# 20190320.net
KiCad netlist of a schematic drawn in EAGLE
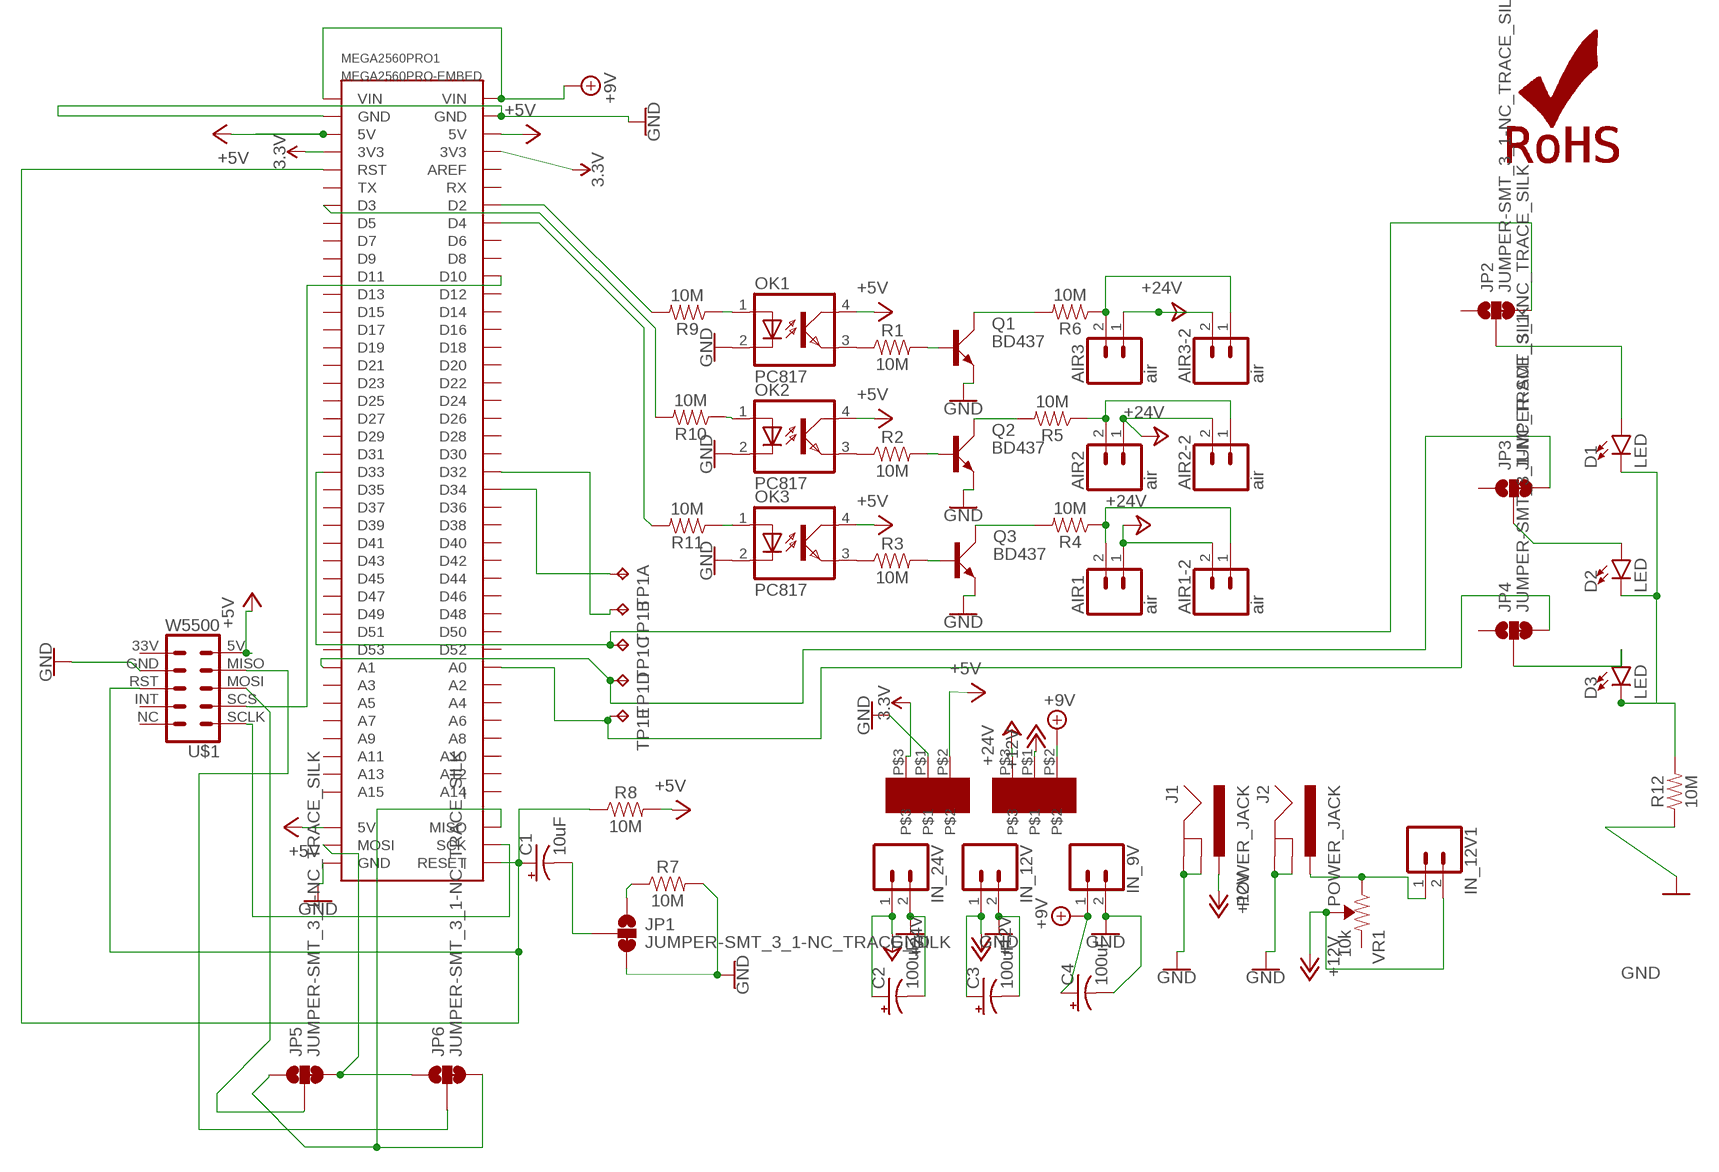
[diagram p0: schematic, sheet 1]

(export (version "E")
  (design (tool "Eeschema 10.0.6"))
  (components
    (comp (ref "AIR1")
      (value "air")
      (footprint "eagle-import:MOLEX-1X2_LOCK")
      (libsource (lib "eagle-import") (part "CONN_02POLAR_LOCK"))
    )
    (comp (ref "AIR1-2")
      (value "air")
      (footprint "eagle-import:1X02")
      (libsource (lib "eagle-import") (part "CONN_02"))
    )
    (comp (ref "AIR2")
      (value "air")
      (footprint "eagle-import:MOLEX-1X2_LOCK")
      (libsource (lib "eagle-import") (part "CONN_02POLAR_LOCK"))
    )
    (comp (ref "AIR2-2")
      (value "air")
      (footprint "eagle-import:1X02")
      (libsource (lib "eagle-import") (part "CONN_02"))
    )
    (comp (ref "AIR3")
      (value "air")
      (footprint "eagle-import:MOLEX-1X2_LOCK")
      (libsource (lib "eagle-import") (part "CONN_02POLAR_LOCK"))
    )
    (comp (ref "AIR3-2")
      (value "air")
      (footprint "eagle-import:1X02")
      (libsource (lib "eagle-import") (part "CONN_02"))
    )
    (comp (ref "C1")
      (value "10uF")
      (footprint "eagle-import:CPOL-RADIAL-2.5MM-5MM-KIT")
      (libsource (lib "eagle-import") (part "10UF-POLAR-RADIAL-2.5MM-KIT-25V-20%"))
    )
    (comp (ref "C2")
      (value "100uF")
      (footprint "eagle-import:CPOL-RADIAL-2.5MM-6.5MM")
      (libsource (lib "eagle-import") (part "100UF-POLAR-RADIAL-2.5MM-25V-20%"))
    )
    (comp (ref "C3")
      (value "100uF")
      (footprint "eagle-import:CPOL-RADIAL-2.5MM-6.5MM")
      (libsource (lib "eagle-import") (part "100UF-POLAR-RADIAL-2.5MM-25V-20%"))
    )
    (comp (ref "C4")
      (value "100uF")
      (footprint "eagle-import:CPOL-RADIAL-2.5MM-6.5MM")
      (libsource (lib "eagle-import") (part "100UF-POLAR-RADIAL-2.5MM-25V-20%"))
    )
    (comp (ref "D1")
      (value "LED")
      (footprint "eagle-import:LED_5MM")
      (libsource (lib "eagle-import") (part "LED5MM"))
    )
    (comp (ref "D2")
      (value "LED")
      (footprint "eagle-import:LED_5MM")
      (libsource (lib "eagle-import") (part "LED5MM"))
    )
    (comp (ref "D3")
      (value "LED")
      (footprint "eagle-import:LED_5MM")
      (libsource (lib "eagle-import") (part "LED5MM"))
    )
    (comp (ref "IN_9V")
      (value "CONN_02POLAR_LOCK")
      (footprint "eagle-import:MOLEX-1X2_LOCK")
      (libsource (lib "eagle-import") (part "CONN_02POLAR_LOCK"))
    )
    (comp (ref "IN_12V")
      (value "CONN_02POLAR_LOCK")
      (footprint "eagle-import:MOLEX-1X2_LOCK")
      (libsource (lib "eagle-import") (part "CONN_02POLAR_LOCK"))
    )
    (comp (ref "IN_12V1")
      (value "CONN_02POLAR_LOCK")
      (footprint "eagle-import:MOLEX-1X2_LOCK")
      (libsource (lib "eagle-import") (part "CONN_02POLAR_LOCK"))
    )
    (comp (ref "IN_24V")
      (value "CONN_02POLAR_LOCK")
      (footprint "eagle-import:MOLEX-1X2_LOCK")
      (libsource (lib "eagle-import") (part "CONN_02POLAR_LOCK"))
    )
    (comp (ref "J1")
      (value "POWER_JACK")
      (footprint "eagle-import:POWER_JACK_PTH")
      (libsource (lib "eagle-import") (part "POWER_JACK"))
    )
    (comp (ref "J2")
      (value "POWER_JACK")
      (footprint "eagle-import:POWER_JACK_PTH")
      (libsource (lib "eagle-import") (part "POWER_JACK"))
    )
    (comp (ref "JP1")
      (value "JUMPER-SMT_3_1-NC_TRACE_SILK")
      (footprint "eagle-import:SMT-JUMPER_3_1-NC_TRACE_SILK")
      (libsource (lib "eagle-import") (part "JUMPER-SMT_3_1-NC_TRACE_SILK"))
    )
    (comp (ref "JP2")
      (value "JUMPER-SMT_3_1-NC_TRACE_SILK")
      (footprint "eagle-import:SMT-JUMPER_3_1-NC_TRACE_SILK")
      (libsource (lib "eagle-import") (part "JUMPER-SMT_3_1-NC_TRACE_SILK"))
    )
    (comp (ref "JP3")
      (value "JUMPER-SMT_3_1-NC_TRACE_SILK")
      (footprint "eagle-import:SMT-JUMPER_3_1-NC_TRACE_SILK")
      (libsource (lib "eagle-import") (part "JUMPER-SMT_3_1-NC_TRACE_SILK"))
    )
    (comp (ref "JP4")
      (value "JUMPER-SMT_3_1-NC_TRACE_SILK")
      (footprint "eagle-import:SMT-JUMPER_3_1-NC_TRACE_SILK")
      (libsource (lib "eagle-import") (part "JUMPER-SMT_3_1-NC_TRACE_SILK"))
    )
    (comp (ref "JP5")
      (value "JUMPER-SMT_3_1-NC_TRACE_SILK")
      (footprint "eagle-import:SMT-JUMPER_3_1-NC_TRACE_SILK")
      (libsource (lib "eagle-import") (part "JUMPER-SMT_3_1-NC_TRACE_SILK"))
    )
    (comp (ref "JP6")
      (value "JUMPER-SMT_3_1-NC_TRACE_SILK")
      (footprint "eagle-import:SMT-JUMPER_3_1-NC_TRACE_SILK")
      (libsource (lib "eagle-import") (part "JUMPER-SMT_3_1-NC_TRACE_SILK"))
    )
    (comp (ref "LOGO1")
      (value "ROHS_LOGO")
      (footprint "eagle-import:ROHS_LOGO_0.18_IN")
      (libsource (lib "eagle-import") (part "ROHS_LOGO"))
    )
    (comp (ref "MEGA2560PRO1")
      (value "MEGA2560PRO-EMBED")
      (footprint "eagle-import:MEGA2560PRO-EMBED")
      (libsource (lib "eagle-import") (part "MEGA2560PRO-EMBED"))
    )
    (comp (ref "OK1")
      (value "PC817")
      (footprint "eagle-import:DIL04")
      (fields (field (name "MPN") "PC817X4J000F"))
      (libsource (lib "eagle-import") (part "PC817"))
    )
    (comp (ref "OK2")
      (value "PC817")
      (footprint "eagle-import:DIL04")
      (fields (field (name "MPN") "PC817X4J000F"))
      (libsource (lib "eagle-import") (part "PC817"))
    )
    (comp (ref "OK3")
      (value "PC817")
      (footprint "eagle-import:DIL04")
      (fields (field (name "MPN") "PC817X4J000F"))
      (libsource (lib "eagle-import") (part "PC817"))
    )
    (comp (ref "Q1")
      (value "BD437")
      (footprint "eagle-import:TO126AV")
      (libsource (lib "eagle-import") (part "BD437"))
    )
    (comp (ref "Q2")
      (value "BD437")
      (footprint "eagle-import:TO126AV")
      (libsource (lib "eagle-import") (part "BD437"))
    )
    (comp (ref "Q3")
      (value "BD437")
      (footprint "eagle-import:TO126AV")
      (libsource (lib "eagle-import") (part "BD437"))
    )
    (comp (ref "R1")
      (value "10M")
      (footprint "eagle-import:AXIAL-0.3")
      (libsource (lib "eagle-import") (part "10MOHM-HORIZ-1/4W-5%"))
    )
    (comp (ref "R2")
      (value "10M")
      (footprint "eagle-import:AXIAL-0.3")
      (libsource (lib "eagle-import") (part "10MOHM-HORIZ-1/4W-5%"))
    )
    (comp (ref "R3")
      (value "10M")
      (footprint "eagle-import:AXIAL-0.3")
      (libsource (lib "eagle-import") (part "10MOHM-HORIZ-1/4W-5%"))
    )
    (comp (ref "R4")
      (value "10M")
      (footprint "eagle-import:AXIAL-0.3")
      (libsource (lib "eagle-import") (part "10MOHM-HORIZ-1/4W-5%"))
    )
    (comp (ref "R5")
      (value "10M")
      (footprint "eagle-import:AXIAL-0.3")
      (libsource (lib "eagle-import") (part "10MOHM-HORIZ-1/4W-5%"))
    )
    (comp (ref "R6")
      (value "10M")
      (footprint "eagle-import:AXIAL-0.3")
      (libsource (lib "eagle-import") (part "10MOHM-HORIZ-1/4W-5%"))
    )
    (comp (ref "R7")
      (value "10M")
      (footprint "eagle-import:AXIAL-0.3")
      (libsource (lib "eagle-import") (part "10MOHM-HORIZ-1/4W-5%"))
    )
    (comp (ref "R8")
      (value "10M")
      (footprint "eagle-import:AXIAL-0.3")
      (libsource (lib "eagle-import") (part "10MOHM-HORIZ-1/4W-5%"))
    )
    (comp (ref "R9")
      (value "10M")
      (footprint "eagle-import:AXIAL-0.3")
      (libsource (lib "eagle-import") (part "10MOHM-HORIZ-1/4W-5%"))
    )
    (comp (ref "R10")
      (value "10M")
      (footprint "eagle-import:AXIAL-0.3")
      (libsource (lib "eagle-import") (part "10MOHM-HORIZ-1/4W-5%"))
    )
    (comp (ref "R11")
      (value "10M")
      (footprint "eagle-import:AXIAL-0.3")
      (libsource (lib "eagle-import") (part "10MOHM-HORIZ-1/4W-5%"))
    )
    (comp (ref "R12")
      (value "10M")
      (footprint "eagle-import:AXIAL-0.3")
      (libsource (lib "eagle-import") (part "10MOHM-HORIZ-1/4W-5%"))
    )
    (comp (ref "TP1")
      (value "TP5P5-25-13")
      (footprint "eagle-import:P5-25-13")
      (libsource (lib "eagle-import") (part "TP5P5-25-13"))
    )
    (comp (ref "U$1")
      (value "W5500")
      (footprint "eagle-import:W5500")
      (libsource (lib "eagle-import") (part "W5500"))
    )
    (comp (ref "U$2")
      (value "AC_3PINAC3PIN7MM")
      (footprint "eagle-import:AC3PIN7MM")
      (libsource (lib "eagle-import") (part "AC_3PINAC3PIN7MM"))
    )
    (comp (ref "U$4")
      (value "AC_3PINAC3PIN7MM")
      (footprint "eagle-import:AC3PIN7MM")
      (libsource (lib "eagle-import") (part "AC_3PINAC3PIN7MM"))
    )
    (comp (ref "VR1")
      (value "10k")
      (footprint "eagle-import:TRIMPOT-PTH-3386U")
      (libsource (lib "eagle-import") (part "TRIMPOT-PTH-10MM-KNOB-1/2W-10%"))
    )
  )
  (nets
    (net (code "1") (name "+5V") (class "Default")
      (node (ref "MEGA2560PRO1") (pin "5V@1") (pinfunction "5V_5V@1") (pintype "bidirectional"))
      (node (ref "MEGA2560PRO1") (pin "5V@2") (pinfunction "5V_5V@2") (pintype "bidirectional"))
      (node (ref "MEGA2560PRO1") (pin "5V@3") (pinfunction "5V_5V@3") (pintype "bidirectional"))
      (node (ref "OK1") (pin "4") (pinfunction "COL_4") (pintype "passive"))
      (node (ref "OK2") (pin "4") (pinfunction "COL_4") (pintype "passive"))
      (node (ref "OK3") (pin "4") (pinfunction "COL_4") (pintype "passive"))
      (node (ref "R8") (pin "P$2") (pinfunction "2_P$2") (pintype "passive"))
      (node (ref "U$1") (pin "5V") (pinfunction "9_5V") (pintype "passive"))
      (node (ref "U$4") (pin "P$2") (pinfunction "P$2_P$2") (pintype "bidirectional"))
    )
    (net (code "2") (name "+9V") (class "Default")
      (node (ref "C4") (pin "1") (pinfunction "+_1") (pintype "passive"))
      (node (ref "IN_9V") (pin "1") (pinfunction "1_1") (pintype "passive"))
      (node (ref "MEGA2560PRO1") (pin "VIN@1") (pinfunction "VIN_VIN@1") (pintype "bidirectional"))
      (node (ref "MEGA2560PRO1") (pin "VIN@2") (pinfunction "VIN_VIN@2") (pintype "bidirectional"))
      (node (ref "U$2") (pin "P$2") (pinfunction "P$2_P$2") (pintype "bidirectional"))
    )
    (net (code "3") (name "+12V") (class "Default")
      (node (ref "C3") (pin "1") (pinfunction "+_1") (pintype "passive"))
      (node (ref "IN_12V") (pin "1") (pinfunction "1_1") (pintype "passive"))
      (node (ref "IN_12V1") (pin "2") (pinfunction "2_2") (pintype "passive"))
      (node (ref "J1") (pin "PWR") (pinfunction "PWR_PWR") (pintype "bidirectional"))
      (node (ref "U$2") (pin "P$1") (pinfunction "P$1_P$1") (pintype "bidirectional"))
      (node (ref "VR1") (pin "2") (pinfunction "WIPER_2") (pintype "passive"))
    )
    (net (code "4") (name "+24V") (class "Default")
      (node (ref "AIR1") (pin "1") (pinfunction "1_1") (pintype "passive"))
      (node (ref "AIR1-2") (pin "2") (pinfunction "2_2") (pintype "passive"))
      (node (ref "AIR2") (pin "1") (pinfunction "1_1") (pintype "passive"))
      (node (ref "AIR2-2") (pin "2") (pinfunction "2_2") (pintype "passive"))
      (node (ref "AIR3") (pin "1") (pinfunction "1_1") (pintype "passive"))
      (node (ref "AIR3-2") (pin "2") (pinfunction "2_2") (pintype "passive"))
      (node (ref "C2") (pin "1") (pinfunction "+_1") (pintype "passive"))
      (node (ref "IN_24V") (pin "1") (pinfunction "1_1") (pintype "passive"))
      (node (ref "U$2") (pin "P$3") (pinfunction "P$3_P$3") (pintype "bidirectional"))
    )
    (net (code "5") (name "3.3V") (class "Default")
      (node (ref "MEGA2560PRO1") (pin "3V3@1") (pinfunction "3V3_3V3@1") (pintype "bidirectional"))
      (node (ref "MEGA2560PRO1") (pin "3V3@2") (pinfunction "3V3_3V3@2") (pintype "bidirectional"))
      (node (ref "U$4") (pin "P$3") (pinfunction "P$3_P$3") (pintype "bidirectional"))
    )
    (net (code "6") (name "GND") (class "Default")
      (node (ref "C2") (pin "2") (pinfunction "-_2") (pintype "passive"))
      (node (ref "C3") (pin "2") (pinfunction "-_2") (pintype "passive"))
      (node (ref "C4") (pin "2") (pinfunction "-_2") (pintype "passive"))
      (node (ref "IN_12V") (pin "2") (pinfunction "2_2") (pintype "passive"))
      (node (ref "IN_24V") (pin "2") (pinfunction "2_2") (pintype "passive"))
      (node (ref "IN_9V") (pin "2") (pinfunction "2_2") (pintype "passive"))
      (node (ref "J1") (pin "GND") (pinfunction "GND_GND") (pintype "bidirectional"))
      (node (ref "J1") (pin "GNDBREAK") (pinfunction "GNDBREAK_GNDBREAK") (pintype "bidirectional"))
      (node (ref "J2") (pin "GND") (pinfunction "GND_GND") (pintype "bidirectional"))
      (node (ref "J2") (pin "GNDBREAK") (pinfunction "GNDBREAK_GNDBREAK") (pintype "bidirectional"))
      (node (ref "JP1") (pin "3") (pinfunction "3_3") (pintype "passive"))
      (node (ref "MEGA2560PRO1") (pin "GND@1") (pinfunction "GND_GND@1") (pintype "bidirectional"))
      (node (ref "MEGA2560PRO1") (pin "GND@2") (pinfunction "GND_GND@2") (pintype "bidirectional"))
      (node (ref "MEGA2560PRO1") (pin "GND@3") (pinfunction "GND_GND@3") (pintype "bidirectional"))
      (node (ref "OK1") (pin "2") (pinfunction "C_2") (pintype "passive"))
      (node (ref "OK2") (pin "2") (pinfunction "C_2") (pintype "passive"))
      (node (ref "OK3") (pin "2") (pinfunction "C_2") (pintype "passive"))
      (node (ref "Q1") (pin "E") (pinfunction "E_E") (pintype "passive"))
      (node (ref "Q2") (pin "E") (pinfunction "E_E") (pintype "passive"))
      (node (ref "Q3") (pin "E") (pinfunction "E_E") (pintype "passive"))
      (node (ref "R12") (pin "P$1") (pinfunction "1_P$1") (pintype "passive"))
      (node (ref "R7") (pin "P$2") (pinfunction "2_P$2") (pintype "passive"))
      (node (ref "U$1") (pin "GND") (pinfunction "8_GND") (pintype "passive"))
      (node (ref "U$4") (pin "P$1") (pinfunction "P$1_P$1") (pintype "bidirectional"))
    )
    (net (code "7") (name "Net-(C1-+)") (class "Default")
      (node (ref "C1") (pin "1") (pinfunction "+_1") (pintype "passive"))
      (node (ref "MEGA2560PRO1") (pin "RESET") (pinfunction "RESET_RESET") (pintype "bidirectional"))
      (node (ref "MEGA2560PRO1") (pin "RST") (pinfunction "RST_RST") (pintype "bidirectional"))
      (node (ref "R8") (pin "P$1") (pinfunction "1_P$1") (pintype "passive"))
      (node (ref "U$1") (pin "RST") (pinfunction "6_RST") (pintype "passive"))
    )
    (net (code "8") (name "Net-(C1--)") (class "Default")
      (node (ref "C1") (pin "2") (pinfunction "-_2") (pintype "passive"))
      (node (ref "JP1") (pin "2") (pinfunction "2_2") (pintype "passive"))
    )
    (net (code "9") (name "Net-(D1-C)") (class "Default")
      (node (ref "D1") (pin "K") (pinfunction "C_K") (pintype "passive"))
      (node (ref "D2") (pin "K") (pinfunction "C_K") (pintype "passive"))
      (node (ref "D3") (pin "K") (pinfunction "C_K") (pintype "passive"))
      (node (ref "R12") (pin "P$2") (pinfunction "2_P$2") (pintype "passive"))
    )
    (net (code "10") (name "Net-(D1-PadA)") (class "Default")
      (node (ref "D1") (pin "A") (pinfunction "A_A") (pintype "passive"))
      (node (ref "JP2") (pin "2") (pinfunction "2_2") (pintype "passive"))
    )
    (net (code "11") (name "Net-(D2-PadA)") (class "Default")
      (node (ref "D2") (pin "A") (pinfunction "A_A") (pintype "passive"))
      (node (ref "JP3") (pin "2") (pinfunction "2_2") (pintype "passive"))
    )
    (net (code "12") (name "Net-(D3-PadA)") (class "Default")
      (node (ref "D3") (pin "A") (pinfunction "A_A") (pintype "passive"))
      (node (ref "JP4") (pin "2") (pinfunction "2_2") (pintype "passive"))
    )
    (net (code "13") (name "Net-(JP5-Pad1)") (class "Default")
      (node (ref "JP5") (pin "1") (pinfunction "1_1") (pintype "passive"))
      (node (ref "JP6") (pin "3") (pinfunction "3_3") (pintype "passive"))
      (node (ref "MEGA2560PRO1") (pin "MISO") (pinfunction "MISO_MISO") (pintype "bidirectional"))
    )
    (net (code "14") (name "Net-(JP5-Pad3)") (class "Default")
      (node (ref "JP5") (pin "3") (pinfunction "3_3") (pintype "passive"))
      (node (ref "JP6") (pin "1") (pinfunction "1_1") (pintype "passive"))
      (node (ref "MEGA2560PRO1") (pin "MOSI") (pinfunction "MOSI_MOSI") (pintype "bidirectional"))
    )
    (net (code "15") (name "Net-(OK1-A)") (class "Default")
      (node (ref "OK1") (pin "1") (pinfunction "A_1") (pintype "passive"))
      (node (ref "R9") (pin "P$1") (pinfunction "1_P$1") (pintype "passive"))
    )
    (net (code "16") (name "Net-(OK1-EMIT)") (class "Default")
      (node (ref "OK1") (pin "3") (pinfunction "EMIT_3") (pintype "passive"))
      (node (ref "R1") (pin "P$1") (pinfunction "1_P$1") (pintype "passive"))
    )
    (net (code "17") (name "Net-(OK2-A)") (class "Default")
      (node (ref "OK2") (pin "1") (pinfunction "A_1") (pintype "passive"))
      (node (ref "R10") (pin "P$1") (pinfunction "1_P$1") (pintype "passive"))
    )
    (net (code "18") (name "Net-(OK2-EMIT)") (class "Default")
      (node (ref "OK2") (pin "3") (pinfunction "EMIT_3") (pintype "passive"))
      (node (ref "R2") (pin "P$1") (pinfunction "1_P$1") (pintype "passive"))
    )
    (net (code "19") (name "Net-(OK3-A)") (class "Default")
      (node (ref "OK3") (pin "1") (pinfunction "A_1") (pintype "passive"))
      (node (ref "R11") (pin "P$1") (pinfunction "1_P$1") (pintype "passive"))
    )
    (net (code "20") (name "Net-(OK3-EMIT)") (class "Default")
      (node (ref "OK3") (pin "3") (pinfunction "EMIT_3") (pintype "passive"))
      (node (ref "R3") (pin "P$1") (pinfunction "1_P$1") (pintype "passive"))
    )
    (net (code "21") (name "Net-(R1-2)") (class "Default")
      (node (ref "Q1") (pin "B") (pinfunction "B_B") (pintype "passive"))
      (node (ref "R1") (pin "P$2") (pinfunction "2_P$2") (pintype "passive"))
    )
    (net (code "22") (name "Net-(R2-2)") (class "Default")
      (node (ref "Q2") (pin "B") (pinfunction "B_B") (pintype "passive"))
      (node (ref "R2") (pin "P$2") (pinfunction "2_P$2") (pintype "passive"))
    )
    (net (code "23") (name "Net-(R3-2)") (class "Default")
      (node (ref "Q3") (pin "B") (pinfunction "B_B") (pintype "passive"))
      (node (ref "R3") (pin "P$2") (pinfunction "2_P$2") (pintype "passive"))
    )
    (net (code "24") (name "Net-(R4-1)") (class "Default")
      (node (ref "AIR1") (pin "2") (pinfunction "2_2") (pintype "passive"))
      (node (ref "AIR1-2") (pin "1") (pinfunction "1_1") (pintype "passive"))
      (node (ref "R4") (pin "P$1") (pinfunction "1_P$1") (pintype "passive"))
    )
    (net (code "25") (name "Net-(R4-2)") (class "Default")
      (node (ref "Q3") (pin "C") (pinfunction "C_C") (pintype "passive"))
      (node (ref "R4") (pin "P$2") (pinfunction "2_P$2") (pintype "passive"))
    )
    (net (code "26") (name "Net-(R5-1)") (class "Default")
      (node (ref "AIR2") (pin "2") (pinfunction "2_2") (pintype "passive"))
      (node (ref "AIR2-2") (pin "1") (pinfunction "1_1") (pintype "passive"))
      (node (ref "R5") (pin "P$1") (pinfunction "1_P$1") (pintype "passive"))
    )
    (net (code "27") (name "Net-(R5-2)") (class "Default")
      (node (ref "Q2") (pin "C") (pinfunction "C_C") (pintype "passive"))
      (node (ref "R5") (pin "P$2") (pinfunction "2_P$2") (pintype "passive"))
    )
    (net (code "28") (name "Net-(R6-1)") (class "Default")
      (node (ref "AIR3") (pin "2") (pinfunction "2_2") (pintype "passive"))
      (node (ref "AIR3-2") (pin "1") (pinfunction "1_1") (pintype "passive"))
      (node (ref "R6") (pin "P$1") (pinfunction "1_P$1") (pintype "passive"))
    )
    (net (code "29") (name "Net-(R6-2)") (class "Default")
      (node (ref "Q1") (pin "C") (pinfunction "C_C") (pintype "passive"))
      (node (ref "R6") (pin "P$2") (pinfunction "2_P$2") (pintype "passive"))
    )
    (net (code "30") (name "Net-(R7-1)") (class "Default")
      (node (ref "JP1") (pin "1") (pinfunction "1_1") (pintype "passive"))
      (node (ref "R7") (pin "P$1") (pinfunction "1_P$1") (pintype "passive"))
    )
    (net (code "31") (name "Net-(R9-2)") (class "Default")
      (node (ref "MEGA2560PRO1") (pin "D2") (pinfunction "D2_D2") (pintype "bidirectional"))
      (node (ref "R9") (pin "P$2") (pinfunction "2_P$2") (pintype "passive"))
    )
    (net (code "32") (name "Net-(R10-2)") (class "Default")
      (node (ref "MEGA2560PRO1") (pin "D3") (pinfunction "D3_D3") (pintype "bidirectional"))
      (node (ref "R10") (pin "P$2") (pinfunction "2_P$2") (pintype "passive"))
    )
    (net (code "33") (name "Net-(R11-2)") (class "Default")
      (node (ref "MEGA2560PRO1") (pin "D4") (pinfunction "D4_D4") (pintype "bidirectional"))
      (node (ref "R11") (pin "P$2") (pinfunction "2_P$2") (pintype "passive"))
    )
    (net (code "34") (name "Net-(TP1A-TP)") (class "Default")
      (node (ref "MEGA2560PRO1") (pin "D34") (pinfunction "D34_D34") (pintype "bidirectional"))
      (node (ref "TP1") (pin "TP-1") (pinfunction "TP_TP-1") (pintype "input"))
    )
    (net (code "35") (name "Net-(TP1B-TP)") (class "Default")
      (node (ref "MEGA2560PRO1") (pin "D32") (pinfunction "D32_D32") (pintype "bidirectional"))
      (node (ref "TP1") (pin "TP-2") (pinfunction "TP_TP-2") (pintype "input"))
    )
    (net (code "36") (name "Net-(TP1C-TP)") (class "Default")
      (node (ref "JP2") (pin "3") (pinfunction "3_3") (pintype "passive"))
      (node (ref "MEGA2560PRO1") (pin "D33") (pinfunction "D33_D33") (pintype "bidirectional"))
      (node (ref "TP1") (pin "TP-3") (pinfunction "TP_TP-3") (pintype "input"))
    )
    (net (code "37") (name "Net-(TP1D-TP)") (class "Default")
      (node (ref "JP3") (pin "3") (pinfunction "3_3") (pintype "passive"))
      (node (ref "MEGA2560PRO1") (pin "A1") (pinfunction "A1_A1") (pintype "bidirectional"))
      (node (ref "TP1") (pin "TP-4") (pinfunction "TP_TP-4") (pintype "input"))
    )
    (net (code "38") (name "Net-(TP1E-TP)") (class "Default")
      (node (ref "JP4") (pin "3") (pinfunction "3_3") (pintype "passive"))
      (node (ref "MEGA2560PRO1") (pin "A0") (pinfunction "A0_A0") (pintype "bidirectional"))
      (node (ref "TP1") (pin "TP-5") (pinfunction "TP_TP-5") (pintype "input"))
    )
    (net (code "39") (name "Net-(U$1-3)") (class "Default")
      (node (ref "MEGA2560PRO1") (pin "D10") (pinfunction "D10_D10") (pintype "bidirectional"))
      (node (ref "U$1") (pin "SCS") (pinfunction "3_SCS") (pintype "passive"))
    )
    (net (code "40") (name "Net-(U$1-5)") (class "Default")
      (node (ref "JP5") (pin "2") (pinfunction "2_2") (pintype "passive"))
      (node (ref "U$1") (pin "MOSI") (pinfunction "5_MOSI") (pintype "passive"))
    )
    (net (code "41") (name "Net-(U$1-7)") (class "Default")
      (node (ref "JP6") (pin "2") (pinfunction "2_2") (pintype "passive"))
      (node (ref "U$1") (pin "MISO") (pinfunction "7_MISO") (pintype "passive"))
    )
    (net (code "42") (name "Net-(U$1-33V)") (class "Default")
      (node (ref "MEGA2560PRO1") (pin "SCK") (pinfunction "SCK_SCK") (pintype "bidirectional"))
      (node (ref "U$1") (pin "SCLK") (pinfunction "33V_SCLK") (pintype "passive"))
    )
    (net (code "43") (name "Net-(VR1-CW)") (class "Default")
      (node (ref "IN_12V1") (pin "1") (pinfunction "1_1") (pintype "passive"))
      (node (ref "J2") (pin "PWR") (pinfunction "PWR_PWR") (pintype "bidirectional"))
      (node (ref "VR1") (pin "3") (pinfunction "CW_3") (pintype "passive"))
    )
    (net (code "44") (name "unconnected-(JP2-Pad1)") (class "Default")
      (node (ref "JP2") (pin "1") (pinfunction "1_1") (pintype "passive"))
    )
    (net (code "45") (name "unconnected-(JP3-Pad1)") (class "Default")
      (node (ref "JP3") (pin "1") (pinfunction "1_1") (pintype "passive"))
    )
    (net (code "46") (name "unconnected-(JP4-Pad1)") (class "Default")
      (node (ref "JP4") (pin "1") (pinfunction "1_1") (pintype "passive"))
    )
    (net (code "47") (name "unconnected-(MEGA2560PRO1-PadA2)") (class "Default")
      (node (ref "MEGA2560PRO1") (pin "A2") (pinfunction "A2_A2") (pintype "bidirectional"))
    )
    (net (code "48") (name "unconnected-(MEGA2560PRO1-PadA3)") (class "Default")
      (node (ref "MEGA2560PRO1") (pin "A3") (pinfunction "A3_A3") (pintype "bidirectional"))
    )
    (net (code "49") (name "unconnected-(MEGA2560PRO1-PadA4)") (class "Default")
      (node (ref "MEGA2560PRO1") (pin "A4") (pinfunction "A4_A4") (pintype "bidirectional"))
    )
    (net (code "50") (name "unconnected-(MEGA2560PRO1-PadA5)") (class "Default")
      (node (ref "MEGA2560PRO1") (pin "A5") (pinfunction "A5_A5") (pintype "bidirectional"))
    )
    (net (code "51") (name "unconnected-(MEGA2560PRO1-PadA6)") (class "Default")
      (node (ref "MEGA2560PRO1") (pin "A6") (pinfunction "A6_A6") (pintype "bidirectional"))
    )
    (net (code "52") (name "unconnected-(MEGA2560PRO1-PadA7)") (class "Default")
      (node (ref "MEGA2560PRO1") (pin "A7") (pinfunction "A7_A7") (pintype "bidirectional"))
    )
    (net (code "53") (name "unconnected-(MEGA2560PRO1-PadA8)") (class "Default")
      (node (ref "MEGA2560PRO1") (pin "A8") (pinfunction "A8_A8") (pintype "bidirectional"))
    )
    (net (code "54") (name "unconnected-(MEGA2560PRO1-PadA9)") (class "Default")
      (node (ref "MEGA2560PRO1") (pin "A9") (pinfunction "A9_A9") (pintype "bidirectional"))
    )
    (net (code "55") (name "unconnected-(MEGA2560PRO1-PadA10)") (class "Default")
      (node (ref "MEGA2560PRO1") (pin "A10") (pinfunction "A10_A10") (pintype "bidirectional"))
    )
    (net (code "56") (name "unconnected-(MEGA2560PRO1-PadA11)") (class "Default")
      (node (ref "MEGA2560PRO1") (pin "A11") (pinfunction "A11_A11") (pintype "bidirectional"))
    )
    (net (code "57") (name "unconnected-(MEGA2560PRO1-PadA12)") (class "Default")
      (node (ref "MEGA2560PRO1") (pin "A12") (pinfunction "A12_A12") (pintype "bidirectional"))
    )
    (net (code "58") (name "unconnected-(MEGA2560PRO1-PadA13)") (class "Default")
      (node (ref "MEGA2560PRO1") (pin "A13") (pinfunction "A13_A13") (pintype "bidirectional"))
    )
    (net (code "59") (name "unconnected-(MEGA2560PRO1-PadA14)") (class "Default")
      (node (ref "MEGA2560PRO1") (pin "A14") (pinfunction "A14_A14") (pintype "bidirectional"))
    )
    (net (code "60") (name "unconnected-(MEGA2560PRO1-PadA15)") (class "Default")
      (node (ref "MEGA2560PRO1") (pin "A15") (pinfunction "A15_A15") (pintype "bidirectional"))
    )
    (net (code "61") (name "unconnected-(MEGA2560PRO1-PadAREF)") (class "Default")
      (node (ref "MEGA2560PRO1") (pin "AREF") (pinfunction "AREF_AREF") (pintype "bidirectional"))
    )
    (net (code "62") (name "unconnected-(MEGA2560PRO1-PadD5)") (class "Default")
      (node (ref "MEGA2560PRO1") (pin "D5") (pinfunction "D5_D5") (pintype "bidirectional"))
    )
    (net (code "63") (name "unconnected-(MEGA2560PRO1-PadD6)") (class "Default")
      (node (ref "MEGA2560PRO1") (pin "D6") (pinfunction "D6_D6") (pintype "bidirectional"))
    )
    (net (code "64") (name "unconnected-(MEGA2560PRO1-PadD7)") (class "Default")
      (node (ref "MEGA2560PRO1") (pin "D7") (pinfunction "D7_D7") (pintype "bidirectional"))
    )
    (net (code "65") (name "unconnected-(MEGA2560PRO1-PadD8)") (class "Default")
      (node (ref "MEGA2560PRO1") (pin "D8") (pinfunction "D8_D8") (pintype "bidirectional"))
    )
    (net (code "66") (name "unconnected-(MEGA2560PRO1-PadD9)") (class "Default")
      (node (ref "MEGA2560PRO1") (pin "D9") (pinfunction "D9_D9") (pintype "bidirectional"))
    )
    (net (code "67") (name "unconnected-(MEGA2560PRO1-PadD11)") (class "Default")
      (node (ref "MEGA2560PRO1") (pin "D11") (pinfunction "D11_D11") (pintype "bidirectional"))
    )
    (net (code "68") (name "unconnected-(MEGA2560PRO1-PadD12)") (class "Default")
      (node (ref "MEGA2560PRO1") (pin "D12") (pinfunction "D12_D12") (pintype "bidirectional"))
    )
    (net (code "69") (name "unconnected-(MEGA2560PRO1-PadD13)") (class "Default")
      (node (ref "MEGA2560PRO1") (pin "D13") (pinfunction "D13_D13") (pintype "bidirectional"))
    )
    (net (code "70") (name "unconnected-(MEGA2560PRO1-PadD14)") (class "Default")
      (node (ref "MEGA2560PRO1") (pin "D14") (pinfunction "D14_D14") (pintype "bidirectional"))
    )
    (net (code "71") (name "unconnected-(MEGA2560PRO1-PadD15)") (class "Default")
      (node (ref "MEGA2560PRO1") (pin "D15") (pinfunction "D15_D15") (pintype "bidirectional"))
    )
    (net (code "72") (name "unconnected-(MEGA2560PRO1-PadD16)") (class "Default")
      (node (ref "MEGA2560PRO1") (pin "D16") (pinfunction "D16_D16") (pintype "bidirectional"))
    )
    (net (code "73") (name "unconnected-(MEGA2560PRO1-PadD17)") (class "Default")
      (node (ref "MEGA2560PRO1") (pin "D17") (pinfunction "D17_D17") (pintype "bidirectional"))
    )
    (net (code "74") (name "unconnected-(MEGA2560PRO1-PadD18)") (class "Default")
      (node (ref "MEGA2560PRO1") (pin "D18") (pinfunction "D18_D18") (pintype "bidirectional"))
    )
    (net (code "75") (name "unconnected-(MEGA2560PRO1-PadD19)") (class "Default")
      (node (ref "MEGA2560PRO1") (pin "D19") (pinfunction "D19_D19") (pintype "bidirectional"))
    )
    (net (code "76") (name "unconnected-(MEGA2560PRO1-PadD20)") (class "Default")
      (node (ref "MEGA2560PRO1") (pin "D20") (pinfunction "D20_D20") (pintype "bidirectional"))
    )
    (net (code "77") (name "unconnected-(MEGA2560PRO1-PadD21)") (class "Default")
      (node (ref "MEGA2560PRO1") (pin "D21") (pinfunction "D21_D21") (pintype "bidirectional"))
    )
    (net (code "78") (name "unconnected-(MEGA2560PRO1-PadD22)") (class "Default")
      (node (ref "MEGA2560PRO1") (pin "D22") (pinfunction "D22_D22") (pintype "bidirectional"))
    )
    (net (code "79") (name "unconnected-(MEGA2560PRO1-PadD23)") (class "Default")
      (node (ref "MEGA2560PRO1") (pin "D23") (pinfunction "D23_D23") (pintype "bidirectional"))
    )
    (net (code "80") (name "unconnected-(MEGA2560PRO1-PadD24)") (class "Default")
      (node (ref "MEGA2560PRO1") (pin "D24") (pinfunction "D24_D24") (pintype "bidirectional"))
    )
    (net (code "81") (name "unconnected-(MEGA2560PRO1-PadD25)") (class "Default")
      (node (ref "MEGA2560PRO1") (pin "D25") (pinfunction "D25_D25") (pintype "bidirectional"))
    )
    (net (code "82") (name "unconnected-(MEGA2560PRO1-PadD26)") (class "Default")
      (node (ref "MEGA2560PRO1") (pin "D26") (pinfunction "D26_D26") (pintype "bidirectional"))
    )
    (net (code "83") (name "unconnected-(MEGA2560PRO1-PadD27)") (class "Default")
      (node (ref "MEGA2560PRO1") (pin "D27") (pinfunction "D27_D27") (pintype "bidirectional"))
    )
    (net (code "84") (name "unconnected-(MEGA2560PRO1-PadD28)") (class "Default")
      (node (ref "MEGA2560PRO1") (pin "D28") (pinfunction "D28_D28") (pintype "bidirectional"))
    )
    (net (code "85") (name "unconnected-(MEGA2560PRO1-PadD29)") (class "Default")
      (node (ref "MEGA2560PRO1") (pin "D29") (pinfunction "D29_D29") (pintype "bidirectional"))
    )
    (net (code "86") (name "unconnected-(MEGA2560PRO1-PadD30)") (class "Default")
      (node (ref "MEGA2560PRO1") (pin "D30") (pinfunction "D30_D30") (pintype "bidirectional"))
    )
    (net (code "87") (name "unconnected-(MEGA2560PRO1-PadD31)") (class "Default")
      (node (ref "MEGA2560PRO1") (pin "D31") (pinfunction "D31_D31") (pintype "bidirectional"))
    )
    (net (code "88") (name "unconnected-(MEGA2560PRO1-PadD35)") (class "Default")
      (node (ref "MEGA2560PRO1") (pin "D35") (pinfunction "D35_D35") (pintype "bidirectional"))
    )
    (net (code "89") (name "unconnected-(MEGA2560PRO1-PadD36)") (class "Default")
      (node (ref "MEGA2560PRO1") (pin "D36") (pinfunction "D36_D36") (pintype "bidirectional"))
    )
    (net (code "90") (name "unconnected-(MEGA2560PRO1-PadD37)") (class "Default")
      (node (ref "MEGA2560PRO1") (pin "D37") (pinfunction "D37_D37") (pintype "bidirectional"))
    )
    (net (code "91") (name "unconnected-(MEGA2560PRO1-PadD38)") (class "Default")
      (node (ref "MEGA2560PRO1") (pin "D38") (pinfunction "D38_D38") (pintype "bidirectional"))
    )
    (net (code "92") (name "unconnected-(MEGA2560PRO1-PadD39)") (class "Default")
      (node (ref "MEGA2560PRO1") (pin "D39") (pinfunction "D39_D39") (pintype "bidirectional"))
    )
    (net (code "93") (name "unconnected-(MEGA2560PRO1-PadD40)") (class "Default")
      (node (ref "MEGA2560PRO1") (pin "D40") (pinfunction "D40_D40") (pintype "bidirectional"))
    )
    (net (code "94") (name "unconnected-(MEGA2560PRO1-PadD41)") (class "Default")
      (node (ref "MEGA2560PRO1") (pin "D41") (pinfunction "D41_D41") (pintype "bidirectional"))
    )
    (net (code "95") (name "unconnected-(MEGA2560PRO1-PadD42)") (class "Default")
      (node (ref "MEGA2560PRO1") (pin "D42") (pinfunction "D42_D42") (pintype "bidirectional"))
    )
    (net (code "96") (name "unconnected-(MEGA2560PRO1-PadD43)") (class "Default")
      (node (ref "MEGA2560PRO1") (pin "D43") (pinfunction "D43_D43") (pintype "bidirectional"))
    )
    (net (code "97") (name "unconnected-(MEGA2560PRO1-PadD44)") (class "Default")
      (node (ref "MEGA2560PRO1") (pin "D44") (pinfunction "D44_D44") (pintype "bidirectional"))
    )
    (net (code "98") (name "unconnected-(MEGA2560PRO1-PadD45)") (class "Default")
      (node (ref "MEGA2560PRO1") (pin "D45") (pinfunction "D45_D45") (pintype "bidirectional"))
    )
    (net (code "99") (name "unconnected-(MEGA2560PRO1-PadD46)") (class "Default")
      (node (ref "MEGA2560PRO1") (pin "D46") (pinfunction "D46_D46") (pintype "bidirectional"))
    )
    (net (code "100") (name "unconnected-(MEGA2560PRO1-PadD47)") (class "Default")
      (node (ref "MEGA2560PRO1") (pin "D47") (pinfunction "D47_D47") (pintype "bidirectional"))
    )
    (net (code "101") (name "unconnected-(MEGA2560PRO1-PadD48)") (class "Default")
      (node (ref "MEGA2560PRO1") (pin "D48") (pinfunction "D48_D48") (pintype "bidirectional"))
    )
    (net (code "102") (name "unconnected-(MEGA2560PRO1-PadD49)") (class "Default")
      (node (ref "MEGA2560PRO1") (pin "D49") (pinfunction "D49_D49") (pintype "bidirectional"))
    )
    (net (code "103") (name "unconnected-(MEGA2560PRO1-PadD50)") (class "Default")
      (node (ref "MEGA2560PRO1") (pin "D50") (pinfunction "D50_D50") (pintype "bidirectional"))
    )
    (net (code "104") (name "unconnected-(MEGA2560PRO1-PadD51)") (class "Default")
      (node (ref "MEGA2560PRO1") (pin "D51") (pinfunction "D51_D51") (pintype "bidirectional"))
    )
    (net (code "105") (name "unconnected-(MEGA2560PRO1-PadD52)") (class "Default")
      (node (ref "MEGA2560PRO1") (pin "D52") (pinfunction "D52_D52") (pintype "bidirectional"))
    )
    (net (code "106") (name "unconnected-(MEGA2560PRO1-PadD53)") (class "Default")
      (node (ref "MEGA2560PRO1") (pin "D53") (pinfunction "D53_D53") (pintype "bidirectional"))
    )
    (net (code "107") (name "unconnected-(MEGA2560PRO1-PadRX)") (class "Default")
      (node (ref "MEGA2560PRO1") (pin "RX") (pinfunction "RX_RX") (pintype "bidirectional"))
    )
    (net (code "108") (name "unconnected-(MEGA2560PRO1-PadTX)") (class "Default")
      (node (ref "MEGA2560PRO1") (pin "TX") (pinfunction "TX_TX") (pintype "bidirectional"))
    )
    (net (code "109") (name "unconnected-(U$1-4-PadINT)") (class "Default")
      (node (ref "U$1") (pin "INT") (pinfunction "4_INT") (pintype "passive"))
    )
    (net (code "110") (name "unconnected-(U$1-5V-PadNC)") (class "Default")
      (node (ref "U$1") (pin "NC") (pinfunction "5V_NC") (pintype "passive"))
    )
    (net (code "111") (name "unconnected-(U$1-10-Pad33V)") (class "Default")
      (node (ref "U$1") (pin "33V") (pinfunction "10_33V") (pintype "passive"))
    )
    (net (code "112") (name "unconnected-(VR1-CCW-Pad1)") (class "Default")
      (node (ref "VR1") (pin "1") (pinfunction "CCW_1") (pintype "passive"))
    )
  )
)
